# Ethernet.net
KiCad netlist of a schematic drawn in Altium Designer
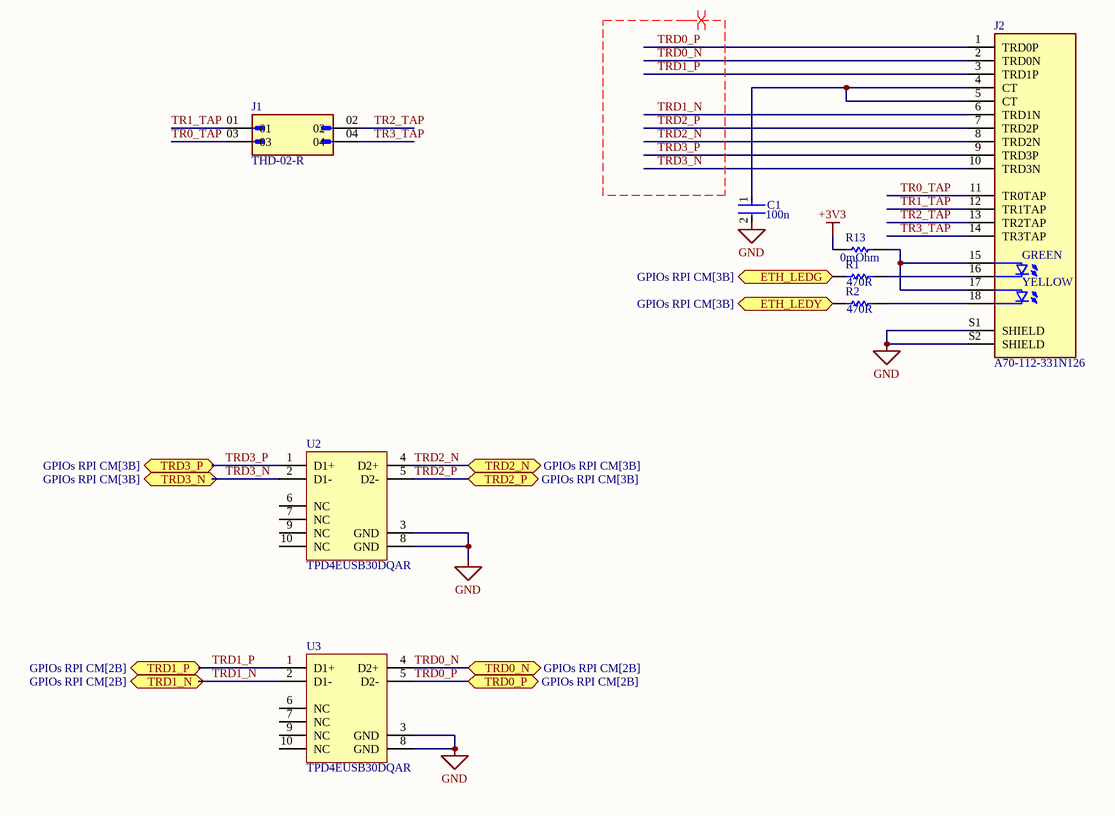
[diagram p0: Ethernet.SchDoc]

(export (version "E")
  (design (tool "Eeschema 10.0.6"))
  (components
    (comp (ref "C1")
      (value "C0402C104K8PACTU")
      (footprint "FP-C0402-BB-MFG")
      (description "CAP CER 0.1UF 10V X5R 0402")
      (fields
        (field (name "CAPACITANCE") "100n")
        (field (name "MANUFACTURER") "Kemet")
        (field (name "TOLERANCE") "0.1")
      )
      (libsource (lib "Altium Content Vault") (part "b4654b650e69147ec39a6b967a45e02"))
    )
    (comp (ref "J1")
      (value "THD-02-R")
      (footprint "VALCON_THD-02-R")
      (description "THD - Valcon 2.54mm Pitch Dual Row Pin Header - Fast Stock")
      (fields (field (name "MF") "Valcon"))
      (libsource (lib "Compute Module 5 ") (part "THD-02-R"))
    )
    (comp (ref "J2")
      (value "A70-112-331N126")
      (footprint "EDAC_A70-112-331N126")
      (description "Ethernet RPI")
      (libsource (lib "Compute Module 5 ") (part "A70-112-331N126"))
    )
    (comp (ref "R1")
      (value "470R")
      (footprint "RESC2013X50X30LL20T20")
      (fields (field (name "MANUFACTURER") "Vishay Dale") (field (name "PART NUMBER") "CRCW0805470RFKEA"))
      (libsource (lib "Altium Content Vault") (part "RES"))
    )
    (comp (ref "R2")
      (value "470R")
      (footprint "RESC2013X50X30LL20T20")
      (fields (field (name "MANUFACTURER") "Vishay Dale") (field (name "PART NUMBER") "CRCW0805470RFKEA"))
      (libsource (lib "Altium Content Vault") (part "RES"))
    )
    (comp (ref "R13")
      (value "ERJ2GE0R00X")
      (footprint "RESC1005X40X25LL05T05")
      (description "Chip Resistor, 0 Ohm, 0.1 W, -55 to 155 degC, 0402 (1005 Metric), RoHS, Tape and Reel")
      (fields
        (field (name "MANUFACTURER") "Panasonic")
        (field (name "RESISTANCE") "0mOhm")
        (field (name "TOLERANCE") "5%")
      )
      (libsource (lib "Altium Content Vault") (part "RES-2"))
    )
    (comp (ref "U2")
      (value "TPD4EUSB30DQAR")
      (footprint "DQA0010A_V")
      (fields (field (name "MANUFACTURER") "Texas Instruments"))
      (libsource (lib "Altium Content Vault") (part "TI-TPD4EUSB30-SON_DQA-10"))
    )
    (comp (ref "U3")
      (value "TPD4EUSB30DQAR")
      (footprint "DQA0010A_V")
      (fields (field (name "MANUFACTURER") "Texas Instruments"))
      (libsource (lib "Altium Content Vault") (part "TI-TPD4EUSB30-SON_DQA-10"))
    )
  )
  (nets
    (net (code "1") (name "+3V3") (class "Default")
      (node (ref "R13") (pin "1") (pinfunction "1_1") (pintype "passive"))
    )
    (net (code "2") (name "/ETH_LEDG") (class "Default")
      (node (ref "R1") (pin "1") (pinfunction "1_1") (pintype "passive"))
    )
    (net (code "3") (name "/ETH_LEDY") (class "Default")
      (node (ref "R2") (pin "1") (pinfunction "1_1") (pintype "passive"))
    )
    (net (code "4") (name "/TR0_TAP") (class "Default")
      (node (ref "J1") (pin "03") (pinfunction "03_03") (pintype "passive"))
      (node (ref "J2") (pin "11") (pinfunction "TR0TAP_11") (pintype "passive"))
    )
    (net (code "5") (name "/TR1_TAP") (class "Default")
      (node (ref "J1") (pin "01") (pinfunction "01_01") (pintype "passive"))
      (node (ref "J2") (pin "12") (pinfunction "TR1TAP_12") (pintype "passive"))
    )
    (net (code "6") (name "/TR2_TAP") (class "Default")
      (node (ref "J1") (pin "02") (pinfunction "02_02") (pintype "passive"))
      (node (ref "J2") (pin "13") (pinfunction "TR2TAP_13") (pintype "passive"))
    )
    (net (code "7") (name "/TR3_TAP") (class "Default")
      (node (ref "J1") (pin "04") (pinfunction "04_04") (pintype "passive"))
      (node (ref "J2") (pin "14") (pinfunction "TR3TAP_14") (pintype "passive"))
    )
    (net (code "8") (name "/TRD0_N") (class "Default")
      (node (ref "J2") (pin "2") (pinfunction "TRD0N_2") (pintype "passive"))
      (node (ref "U3") (pin "4") (pinfunction "D2+_4") (pintype "passive"))
    )
    (net (code "9") (name "/TRD0_P") (class "Default")
      (node (ref "J2") (pin "1") (pinfunction "TRD0P_1") (pintype "passive"))
      (node (ref "U3") (pin "5") (pinfunction "D2-_5") (pintype "passive"))
    )
    (net (code "10") (name "/TRD1_N") (class "Default")
      (node (ref "J2") (pin "6") (pinfunction "TRD1N_6") (pintype "passive"))
      (node (ref "U3") (pin "2") (pinfunction "D1-_2") (pintype "passive"))
    )
    (net (code "11") (name "/TRD1_P") (class "Default")
      (node (ref "J2") (pin "3") (pinfunction "TRD1P_3") (pintype "passive"))
      (node (ref "U3") (pin "1") (pinfunction "D1+_1") (pintype "passive"))
    )
    (net (code "12") (name "/TRD2_N") (class "Default")
      (node (ref "J2") (pin "8") (pinfunction "TRD2N_8") (pintype "passive"))
      (node (ref "U2") (pin "4") (pinfunction "D2+_4") (pintype "passive"))
    )
    (net (code "13") (name "/TRD2_P") (class "Default")
      (node (ref "J2") (pin "7") (pinfunction "TRD2P_7") (pintype "passive"))
      (node (ref "U2") (pin "5") (pinfunction "D2-_5") (pintype "passive"))
    )
    (net (code "14") (name "/TRD3_N") (class "Default")
      (node (ref "J2") (pin "10") (pinfunction "TRD3N_10") (pintype "passive"))
      (node (ref "U2") (pin "2") (pinfunction "D1-_2") (pintype "passive"))
    )
    (net (code "15") (name "/TRD3_P") (class "Default")
      (node (ref "J2") (pin "9") (pinfunction "TRD3P_9") (pintype "passive"))
      (node (ref "U2") (pin "1") (pinfunction "D1+_1") (pintype "passive"))
    )
    (net (code "16") (name "GND") (class "Default")
      (node (ref "C1") (pin "2") (pinfunction "2_2") (pintype "passive"))
      (node (ref "J2") (pin "S1") (pinfunction "SHIELD_S1") (pintype "passive"))
      (node (ref "J2") (pin "S2") (pinfunction "SHIELD_S2") (pintype "passive"))
      (node (ref "U2") (pin "3") (pinfunction "GND_3") (pintype "power_in"))
      (node (ref "U2") (pin "8") (pinfunction "GND_8") (pintype "power_in"))
      (node (ref "U3") (pin "3") (pinfunction "GND_3") (pintype "power_in"))
      (node (ref "U3") (pin "8") (pinfunction "GND_8") (pintype "power_in"))
    )
    (net (code "17") (name "Net-(C1-Pad1)") (class "Default")
      (node (ref "C1") (pin "1") (pinfunction "1_1") (pintype "passive"))
      (node (ref "J2") (pin "4") (pinfunction "CT_4") (pintype "passive"))
      (node (ref "J2") (pin "5") (pinfunction "CT_5") (pintype "passive"))
    )
    (net (code "18") (name "Net-(J2-Anode-Pad15)") (class "Default")
      (node (ref "J2") (pin "15") (pinfunction "Anode_15") (pintype "passive"))
      (node (ref "J2") (pin "17") (pinfunction "Anode_17") (pintype "passive"))
      (node (ref "R13") (pin "2") (pinfunction "2_2") (pintype "passive"))
    )
    (net (code "19") (name "Net-(J2-Cathode-Pad16)") (class "Default")
      (node (ref "J2") (pin "16") (pinfunction "Cathode_16") (pintype "passive"))
      (node (ref "R1") (pin "2") (pinfunction "2_2") (pintype "passive"))
    )
    (net (code "20") (name "Net-(J2-Cathode-Pad18)") (class "Default")
      (node (ref "J2") (pin "18") (pinfunction "Cathode_18") (pintype "passive"))
      (node (ref "R2") (pin "2") (pinfunction "2_2") (pintype "passive"))
    )
    (net (code "21") (name "unconnected-(U2-NC-Pad6)") (class "Default")
      (node (ref "U2") (pin "6") (pinfunction "NC_6") (pintype "passive"))
    )
    (net (code "22") (name "unconnected-(U2-NC-Pad7)") (class "Default")
      (node (ref "U2") (pin "7") (pinfunction "NC_7") (pintype "passive"))
    )
    (net (code "23") (name "unconnected-(U2-NC-Pad9)") (class "Default")
      (node (ref "U2") (pin "9") (pinfunction "NC_9") (pintype "passive"))
    )
    (net (code "24") (name "unconnected-(U2-NC-Pad10)") (class "Default")
      (node (ref "U2") (pin "10") (pinfunction "NC_10") (pintype "passive"))
    )
    (net (code "25") (name "unconnected-(U3-NC-Pad6)") (class "Default")
      (node (ref "U3") (pin "6") (pinfunction "NC_6") (pintype "passive"))
    )
    (net (code "26") (name "unconnected-(U3-NC-Pad7)") (class "Default")
      (node (ref "U3") (pin "7") (pinfunction "NC_7") (pintype "passive"))
    )
    (net (code "27") (name "unconnected-(U3-NC-Pad9)") (class "Default")
      (node (ref "U3") (pin "9") (pinfunction "NC_9") (pintype "passive"))
    )
    (net (code "28") (name "unconnected-(U3-NC-Pad10)") (class "Default")
      (node (ref "U3") (pin "10") (pinfunction "NC_10") (pintype "passive"))
    )
  )
)
